# Sheet.net
KiCad netlist of a schematic drawn in Altium Designer
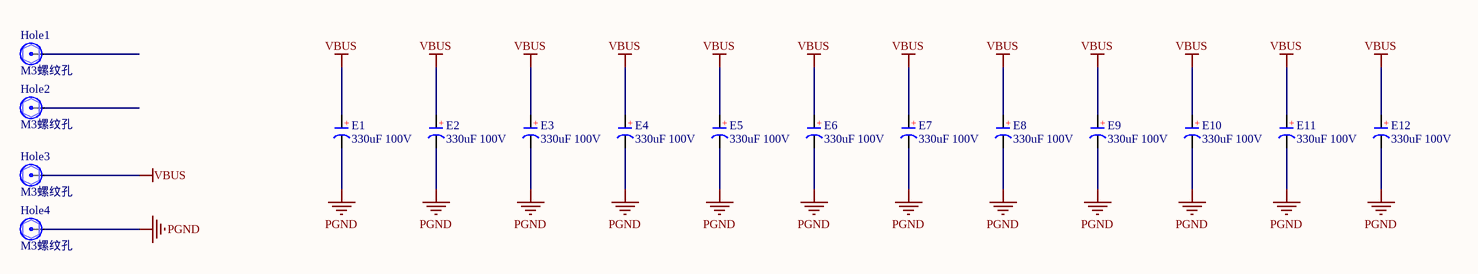
[diagram p0: Sheet.SchDoc]

(export (version "E")
  (design (tool "Eeschema 10.0.6"))
  (components
    (comp (ref "E1")
      (value "330uF 100V")
      (footprint "13*25插件电解电容 卧式")
      (description "贴片钽电容")
      (fields (field (name "版权归属") "源创客"))
      (libsource (lib "Capacitor") (part "C-CD"))
    )
    (comp (ref "E2")
      (value "330uF 100V")
      (footprint "13*25插件电解电容 卧式")
      (description "贴片钽电容")
      (fields (field (name "版权归属") "源创客"))
      (libsource (lib "Capacitor") (part "C-CD"))
    )
    (comp (ref "E3")
      (value "330uF 100V")
      (footprint "13*25插件电解电容 卧式")
      (description "贴片钽电容")
      (fields (field (name "版权归属") "源创客"))
      (libsource (lib "Capacitor") (part "C-CD"))
    )
    (comp (ref "E4")
      (value "330uF 100V")
      (footprint "13*25插件电解电容 卧式")
      (description "贴片钽电容")
      (fields (field (name "版权归属") "源创客"))
      (libsource (lib "Capacitor") (part "C-CD"))
    )
    (comp (ref "E5")
      (value "330uF 100V")
      (footprint "13*25插件电解电容 卧式")
      (description "贴片钽电容")
      (fields (field (name "版权归属") "源创客"))
      (libsource (lib "Capacitor") (part "C-CD"))
    )
    (comp (ref "E6")
      (value "330uF 100V")
      (footprint "13*25插件电解电容 卧式")
      (description "贴片钽电容")
      (fields (field (name "版权归属") "源创客"))
      (libsource (lib "Capacitor") (part "C-CD"))
    )
    (comp (ref "E7")
      (value "330uF 100V")
      (footprint "13*25插件电解电容 卧式")
      (description "贴片钽电容")
      (fields (field (name "版权归属") "源创客"))
      (libsource (lib "Capacitor") (part "C-CD"))
    )
    (comp (ref "E8")
      (value "330uF 100V")
      (footprint "13*25插件电解电容 卧式")
      (description "贴片钽电容")
      (fields (field (name "版权归属") "源创客"))
      (libsource (lib "Capacitor") (part "C-CD"))
    )
    (comp (ref "E9")
      (value "330uF 100V")
      (footprint "13*25插件电解电容 卧式")
      (description "贴片钽电容")
      (fields (field (name "版权归属") "源创客"))
      (libsource (lib "Capacitor") (part "C-CD"))
    )
    (comp (ref "E10")
      (value "330uF 100V")
      (footprint "13*25插件电解电容 卧式")
      (description "贴片钽电容")
      (fields (field (name "版权归属") "源创客"))
      (libsource (lib "Capacitor") (part "C-CD"))
    )
    (comp (ref "E11")
      (value "330uF 100V")
      (footprint "13*25插件电解电容 卧式")
      (description "贴片钽电容")
      (fields (field (name "版权归属") "源创客"))
      (libsource (lib "Capacitor") (part "C-CD"))
    )
    (comp (ref "E12")
      (value "330uF 100V")
      (footprint "13*25插件电解电容 卧式")
      (description "贴片钽电容")
      (fields (field (name "版权归属") "源创客"))
      (libsource (lib "Capacitor") (part "C-CD"))
    )
    (comp (ref "Hole1") (value "M3螺纹孔") (footprint "M3_3*7载流孔_螺丝") (libsource (lib "Hole") (part "M3螺纹孔")))
    (comp (ref "Hole2") (value "M3螺纹孔") (footprint "M3_3*7载流孔_螺丝") (libsource (lib "Hole") (part "M3螺纹孔")))
    (comp (ref "Hole3") (value "M3螺纹孔") (footprint "M3_3*7载流孔_螺丝") (libsource (lib "Hole") (part "M3螺纹孔")))
    (comp (ref "Hole4") (value "M3螺纹孔") (footprint "M3_3*7载流孔_螺丝") (libsource (lib "Hole") (part "M3螺纹孔")))
  )
  (nets
    (net (code "1") (name "PGND") (class "Default")
      (node (ref "E1") (pin "2") (pinfunction "K_2") (pintype "passive"))
      (node (ref "E10") (pin "2") (pinfunction "K_2") (pintype "passive"))
      (node (ref "E11") (pin "2") (pinfunction "K_2") (pintype "passive"))
      (node (ref "E12") (pin "2") (pinfunction "K_2") (pintype "passive"))
      (node (ref "E2") (pin "2") (pinfunction "K_2") (pintype "passive"))
      (node (ref "E3") (pin "2") (pinfunction "K_2") (pintype "passive"))
      (node (ref "E4") (pin "2") (pinfunction "K_2") (pintype "passive"))
      (node (ref "E5") (pin "2") (pinfunction "K_2") (pintype "passive"))
      (node (ref "E6") (pin "2") (pinfunction "K_2") (pintype "passive"))
      (node (ref "E7") (pin "2") (pinfunction "K_2") (pintype "passive"))
      (node (ref "E8") (pin "2") (pinfunction "K_2") (pintype "passive"))
      (node (ref "E9") (pin "2") (pinfunction "K_2") (pintype "passive"))
      (node (ref "Hole4") (pin "1") (pinfunction "1_1") (pintype "passive"))
    )
    (net (code "2") (name "VBUS") (class "Default")
      (node (ref "E1") (pin "1") (pinfunction "A_1") (pintype "passive"))
      (node (ref "E10") (pin "1") (pinfunction "A_1") (pintype "passive"))
      (node (ref "E11") (pin "1") (pinfunction "A_1") (pintype "passive"))
      (node (ref "E12") (pin "1") (pinfunction "A_1") (pintype "passive"))
      (node (ref "E2") (pin "1") (pinfunction "A_1") (pintype "passive"))
      (node (ref "E3") (pin "1") (pinfunction "A_1") (pintype "passive"))
      (node (ref "E4") (pin "1") (pinfunction "A_1") (pintype "passive"))
      (node (ref "E5") (pin "1") (pinfunction "A_1") (pintype "passive"))
      (node (ref "E6") (pin "1") (pinfunction "A_1") (pintype "passive"))
      (node (ref "E7") (pin "1") (pinfunction "A_1") (pintype "passive"))
      (node (ref "E8") (pin "1") (pinfunction "A_1") (pintype "passive"))
      (node (ref "E9") (pin "1") (pinfunction "A_1") (pintype "passive"))
      (node (ref "Hole3") (pin "1") (pinfunction "1_1") (pintype "passive"))
    )
    (net (code "3") (name "unconnected-(Hole1-Pad1)") (class "Default")
      (node (ref "Hole1") (pin "1") (pinfunction "1_1") (pintype "passive"))
    )
    (net (code "4") (name "unconnected-(Hole2-Pad1)") (class "Default")
      (node (ref "Hole2") (pin "1") (pinfunction "1_1") (pintype "passive"))
    )
  )
)
